# design.net
KiCad netlist of a schematic drawn in Altium Designer
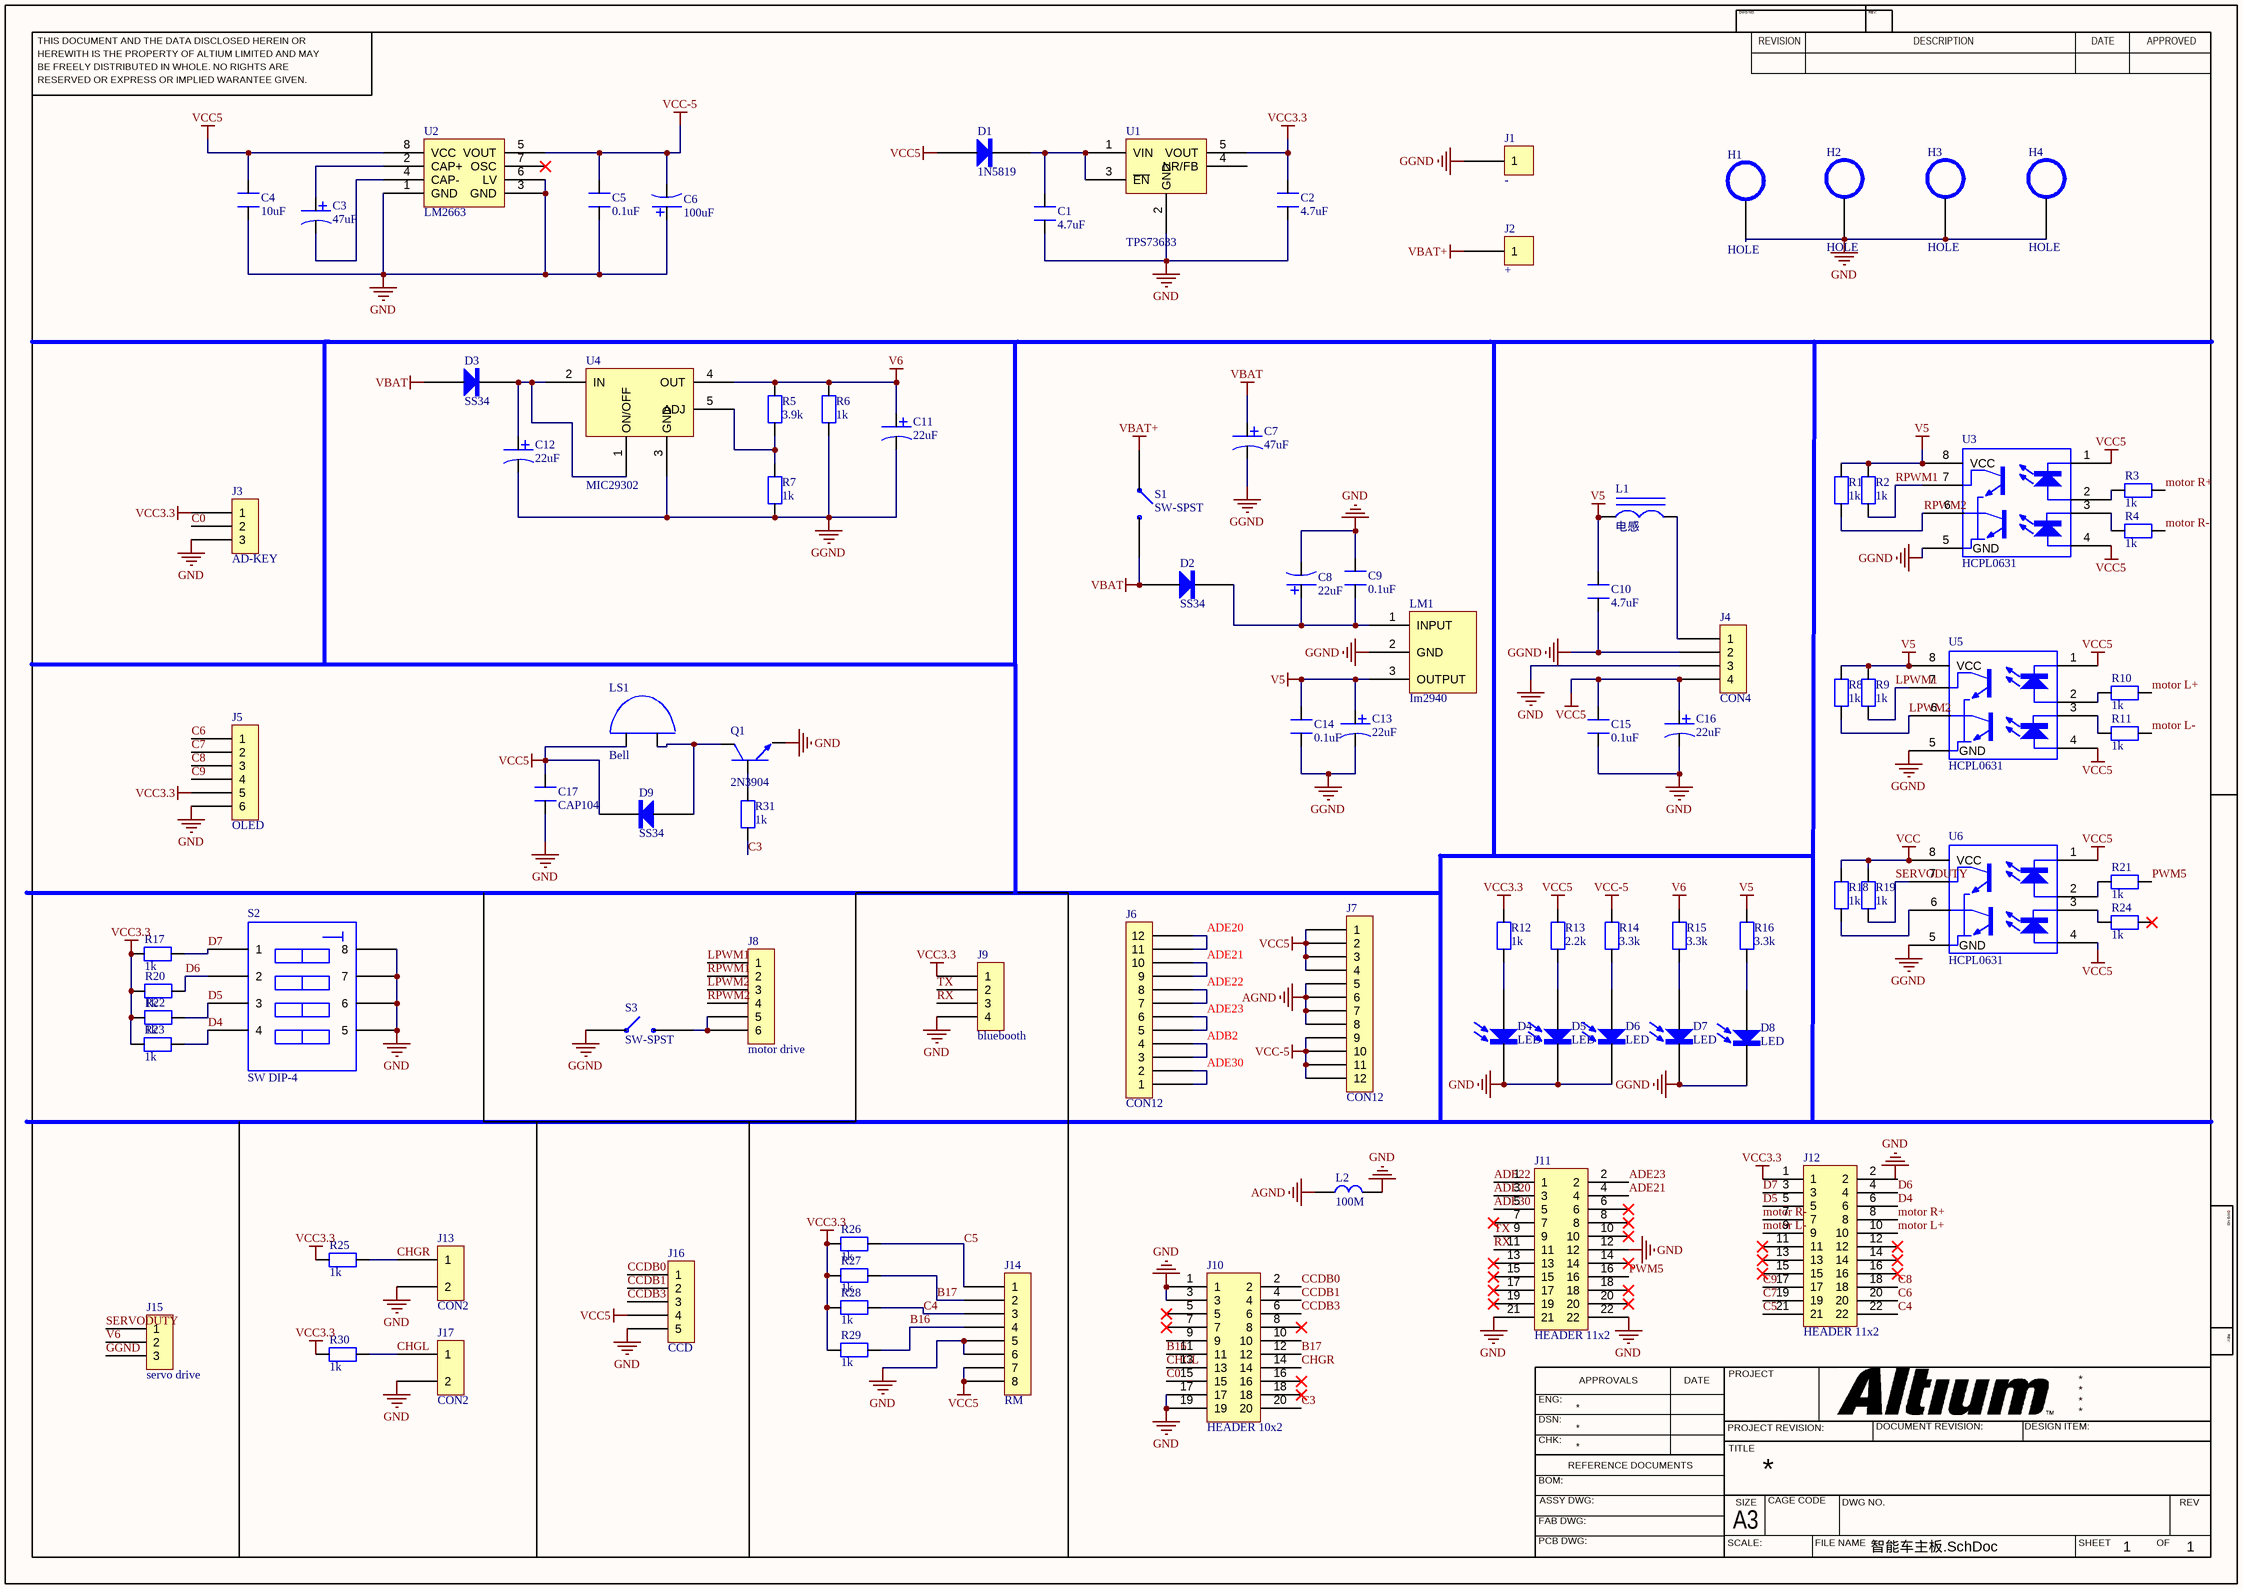
[diagram p0: 智能车主板.SchDoc]

(export (version "E")
  (design (tool "Eeschema 10.0.6"))
  (components
    (comp (ref "C1")
      (value "4.7uF")
      (footprint "0805C")
      (description "电容")
      (libsource (lib "智能车主板") (part "CAP"))
    )
    (comp (ref "C2")
      (value "4.7uF")
      (footprint "0805C")
      (description "电容")
      (libsource (lib "智能车主板") (part "CAP"))
    )
    (comp (ref "C3") (value "47uF") (footprint "B型钽电容_3528_21") (libsource (lib "智能车主板") (part "极性电容")))
    (comp (ref "C4")
      (value "10uF")
      (footprint "0805C")
      (description "电容")
      (libsource (lib "智能车主板") (part "CAP"))
    )
    (comp (ref "C5")
      (value "0.1uF")
      (footprint "0805C")
      (description "电容")
      (libsource (lib "智能车主板") (part "CAP"))
    )
    (comp (ref "C6") (value "100uF") (footprint "B型钽电容_3528_21") (libsource (lib "智能车主板") (part "极性电容")))
    (comp (ref "C7") (value "47uF") (footprint "B型钽电容_3528_21") (libsource (lib "智能车主板") (part "极性电容")))
    (comp (ref "C8") (value "22uF") (footprint "B型钽电容_3528_21") (libsource (lib "智能车主板") (part "极性电容")))
    (comp (ref "C9")
      (value "0.1uF")
      (footprint "0805C")
      (description "电容")
      (libsource (lib "智能车主板") (part "CAP"))
    )
    (comp (ref "C10")
      (value "4.7uF")
      (footprint "0805C")
      (description "电容")
      (libsource (lib "智能车主板") (part "CAP"))
    )
    (comp (ref "C11") (value "22uF") (footprint "B型钽电容_3528_21") (libsource (lib "智能车主板") (part "极性电容")))
    (comp (ref "C12") (value "22uF") (footprint "B型钽电容_3528_21") (libsource (lib "智能车主板") (part "极性电容")))
    (comp (ref "C13") (value "22uF") (footprint "B型钽电容_3528_21") (libsource (lib "智能车主板") (part "极性电容")))
    (comp (ref "C14")
      (value "0.1uF")
      (footprint "0805C")
      (description "电容")
      (libsource (lib "智能车主板") (part "CAP"))
    )
    (comp (ref "C15")
      (value "0.1uF")
      (footprint "0805C")
      (description "电容")
      (libsource (lib "智能车主板") (part "CAP"))
    )
    (comp (ref "C16") (value "22uF") (footprint "B型钽电容_3528_21") (libsource (lib "智能车主板") (part "极性电容")))
    (comp (ref "C17")
      (value "CAP104")
      (footprint "0805C")
      (description "电容")
      (libsource (lib "智能车主板") (part "CAP"))
    )
    (comp (ref "D1")
      (value "1N5819")
      (footprint "SOD-123")
      (description "二极管")
      (libsource (lib "智能车主板") (part "SS34"))
    )
    (comp (ref "D2")
      (value "SS34")
      (footprint "SOD-123")
      (description "二极管")
      (libsource (lib "智能车主板") (part "SS34"))
    )
    (comp (ref "D3")
      (value "SS34")
      (footprint "SOD-123")
      (description "二极管")
      (libsource (lib "智能车主板") (part "SS34"))
    )
    (comp (ref "D4") (value "LED") (footprint "0805D") (libsource (lib "智能车主板") (part "LED")))
    (comp (ref "D5") (value "LED") (footprint "0805D") (libsource (lib "智能车主板") (part "LED")))
    (comp (ref "D6") (value "LED") (footprint "0805D") (libsource (lib "智能车主板") (part "LED")))
    (comp (ref "D7") (value "LED") (footprint "0805D") (libsource (lib "智能车主板") (part "LED")))
    (comp (ref "D8") (value "LED") (footprint "0805D") (libsource (lib "智能车主板") (part "LED")))
    (comp (ref "D9")
      (value "SS34")
      (footprint "SOD-123")
      (description "二极管")
      (libsource (lib "智能车主板") (part "SS34"))
    )
    (comp (ref "H1") (value "HOLE") (footprint "铜柱孔3") (libsource (lib "智能车主板") (part "固定孔")))
    (comp (ref "H2") (value "HOLE") (footprint "铜柱孔3") (libsource (lib "智能车主板") (part "固定孔")))
    (comp (ref "H3") (value "HOLE") (footprint "铜柱孔3") (libsource (lib "智能车主板") (part "固定孔")))
    (comp (ref "H4") (value "HOLE") (footprint "铜柱孔3") (libsource (lib "智能车主板") (part "固定孔")))
    (comp (ref "J1") (value "-") (footprint "单面焊盘2*3MM_1PIN") (libsource (lib "智能车主板") (part "CON1")))
    (comp (ref "J2") (value "+") (footprint "单面焊盘2*3MM_1PIN") (libsource (lib "智能车主板") (part "CON1")))
    (comp (ref "J3") (value "AD-KEY") (footprint "HDR1X3") (libsource (lib "智能车主板") (part "CON3")))
    (comp (ref "J4") (value "CON4") (footprint "HDR1X4") (libsource (lib "智能车主板") (part "CON4")))
    (comp (ref "J5") (value "OLED") (footprint "HDR2X3") (libsource (lib "智能车主板") (part "CON6")))
    (comp (ref "J6") (value "CON12") (footprint "HDR2X6") (libsource (lib "") (part "CON12_1")))
    (comp (ref "J7") (value "CON12") (footprint "HDR2X6") (libsource (lib "智能车主板") (part "CON12")))
    (comp (ref "J8") (value "motor drive") (footprint "HDR2X3") (libsource (lib "智能车主板") (part "CON6")))
    (comp (ref "J9") (value "bluebooth") (footprint "HDR1X4") (libsource (lib "智能车主板") (part "CON4")))
    (comp (ref "J10")
      (value "HEADER 10x2")
      (footprint "HDR2X10")
      (description "排针")
      (libsource (lib "智能车主板") (part "HEADER 10x2"))
    )
    (comp (ref "J11")
      (value "HEADER 11x2")
      (footprint "HDR2X11")
      (description "排针")
      (libsource (lib "智能车主板") (part "HEADER 11x2"))
    )
    (comp (ref "J12")
      (value "HEADER 11x2")
      (footprint "HDR2X11")
      (description "排针")
      (libsource (lib "智能车主板") (part "HEADER 11x2"))
    )
    (comp (ref "J13") (value "CON2") (footprint "2PIN杜邦插座_1.27mm") (libsource (lib "智能车主板") (part "CON2")))
    (comp (ref "J14") (value "RM") (footprint "HDR2X4") (libsource (lib "智能车主板") (part "CON8")))
    (comp (ref "J15") (value "servo drive") (footprint "HDR1X3") (libsource (lib "智能车主板") (part "CON3")))
    (comp (ref "J16") (value "CCD") (footprint "HDR1X5") (libsource (lib "智能车主板") (part "CON5")))
    (comp (ref "J17") (value "CON2") (footprint "2PIN杜邦插座_1.27mm") (libsource (lib "智能车主板") (part "CON2")))
    (comp (ref "L1") (value "电感") (footprint "CDRH3D16_4.2*1.8") (libsource (lib "智能车主板") (part "INDUCTOR")))
    (comp (ref "L2") (value "100M") (footprint "0603L") (libsource (lib "智能车主板") (part "INDUCTOR_2")))
    (comp (ref "LM1")
      (value "Im2940")
      (footprint "SOT-223")
      (description "IC")
      (libsource (lib "智能车主板") (part "Im2940"))
    )
    (comp (ref "LS1") (value "Bell") (footprint "蜂鸣器侧装") (libsource (lib "智能车主板") (part "Bell")))
    (comp (ref "Q1")
      (value "2N3904")
      (footprint "TO-92A")
      (description "NPN General Purpose Amplifier")
      (libsource (lib "智能车主板") (part "2N3904"))
    )
    (comp (ref "R1")
      (value "1k")
      (footprint "0805_Res")
      (description "电阻")
      (libsource (lib "") (part "RES_1"))
    )
    (comp (ref "R2")
      (value "1k")
      (footprint "0805_Res")
      (description "电阻")
      (libsource (lib "") (part "RES_1"))
    )
    (comp (ref "R3")
      (value "1k")
      (footprint "0805_Res")
      (description "电阻")
      (libsource (lib "智能车主板") (part "RES"))
    )
    (comp (ref "R4")
      (value "1k")
      (footprint "0805_Res")
      (description "电阻")
      (libsource (lib "智能车主板") (part "RES"))
    )
    (comp (ref "R5")
      (value "3.9k")
      (footprint "0805_Res")
      (description "电阻")
      (libsource (lib "") (part "RES_1"))
    )
    (comp (ref "R6")
      (value "1k")
      (footprint "0805_Res")
      (description "电阻")
      (libsource (lib "") (part "RES_1"))
    )
    (comp (ref "R7")
      (value "1k")
      (footprint "0805_Res")
      (description "电阻")
      (libsource (lib "") (part "RES_1"))
    )
    (comp (ref "R8")
      (value "1k")
      (footprint "0805_Res")
      (description "电阻")
      (libsource (lib "") (part "RES_1"))
    )
    (comp (ref "R9")
      (value "1k")
      (footprint "0805_Res")
      (description "电阻")
      (libsource (lib "") (part "RES_1"))
    )
    (comp (ref "R10")
      (value "1k")
      (footprint "0805_Res")
      (description "电阻")
      (libsource (lib "智能车主板") (part "RES"))
    )
    (comp (ref "R11")
      (value "1k")
      (footprint "0805_Res")
      (description "电阻")
      (libsource (lib "智能车主板") (part "RES"))
    )
    (comp (ref "R12")
      (value "1k")
      (footprint "0805_Res")
      (description "电阻")
      (libsource (lib "") (part "RES_1"))
    )
    (comp (ref "R13")
      (value "2.2k")
      (footprint "0805_Res")
      (description "电阻")
      (libsource (lib "") (part "RES_1"))
    )
    (comp (ref "R14")
      (value "3.3k")
      (footprint "0805_Res")
      (description "电阻")
      (libsource (lib "") (part "RES_1"))
    )
    (comp (ref "R15")
      (value "3.3k")
      (footprint "0805_Res")
      (description "电阻")
      (libsource (lib "") (part "RES_1"))
    )
    (comp (ref "R16")
      (value "3.3k")
      (footprint "0805_Res")
      (description "电阻")
      (libsource (lib "") (part "RES_1"))
    )
    (comp (ref "R17")
      (value "1k")
      (footprint "0805_Res")
      (description "电阻")
      (libsource (lib "智能车主板") (part "RES"))
    )
    (comp (ref "R18")
      (value "1k")
      (footprint "0805_Res")
      (description "电阻")
      (libsource (lib "") (part "RES_1"))
    )
    (comp (ref "R19")
      (value "1k")
      (footprint "0805_Res")
      (description "电阻")
      (libsource (lib "") (part "RES_1"))
    )
    (comp (ref "R20")
      (value "1k")
      (footprint "0805_Res")
      (description "电阻")
      (libsource (lib "智能车主板") (part "RES"))
    )
    (comp (ref "R21")
      (value "1k")
      (footprint "0805_Res")
      (description "电阻")
      (libsource (lib "智能车主板") (part "RES"))
    )
    (comp (ref "R22")
      (value "1k")
      (footprint "0805_Res")
      (description "电阻")
      (libsource (lib "智能车主板") (part "RES"))
    )
    (comp (ref "R23")
      (value "1k")
      (footprint "0805_Res")
      (description "电阻")
      (libsource (lib "智能车主板") (part "RES"))
    )
    (comp (ref "R24")
      (value "1k")
      (footprint "0805_Res")
      (description "电阻")
      (libsource (lib "智能车主板") (part "RES"))
    )
    (comp (ref "R25")
      (value "1k")
      (footprint "0805_Res")
      (description "电阻")
      (libsource (lib "智能车主板") (part "RES"))
    )
    (comp (ref "R26")
      (value "1k")
      (footprint "0805_Res")
      (description "电阻")
      (libsource (lib "智能车主板") (part "RES"))
    )
    (comp (ref "R27")
      (value "1k")
      (footprint "0805_Res")
      (description "电阻")
      (libsource (lib "智能车主板") (part "RES"))
    )
    (comp (ref "R28")
      (value "1k")
      (footprint "0805_Res")
      (description "电阻")
      (libsource (lib "智能车主板") (part "RES"))
    )
    (comp (ref "R29")
      (value "1k")
      (footprint "0805_Res")
      (description "电阻")
      (libsource (lib "智能车主板") (part "RES"))
    )
    (comp (ref "R30")
      (value "1k")
      (footprint "0805_Res")
      (description "电阻")
      (libsource (lib "智能车主板") (part "RES"))
    )
    (comp (ref "R31")
      (value "1k")
      (footprint "0805_Res")
      (description "电阻")
      (libsource (lib "") (part "RES_1"))
    )
    (comp (ref "S1") (value "SW-SPST") (footprint "开关") (libsource (lib "智能车主板") (part "SW-SPST")))
    (comp (ref "S2") (value "SW DIP-4") (footprint "4路拨码开关") (libsource (lib "智能车主板") (part "SW DIP-4")))
    (comp (ref "S3") (value "SW-SPST") (footprint "开关") (libsource (lib "智能车主板") (part "SW-SPST")))
    (comp (ref "U1")
      (value "TPS73633")
      (footprint "SOT23_5-LEADS")
      (description "IC")
      (libsource (lib "智能车主板") (part "TPS73633"))
    )
    (comp (ref "U2")
      (value "LM2663")
      (footprint "SOP-8")
      (description "IC")
      (libsource (lib "智能车主板") (part "LM2663"))
    )
    (comp (ref "U3")
      (value "HCPL0631")
      (footprint "SOP-8")
      (description "光耦")
      (libsource (lib "智能车主板") (part "HCPL0631"))
    )
    (comp (ref "U4")
      (value "MIC29302")
      (footprint "TO_263_5(10.5*8.4mm)")
      (description "IC")
      (libsource (lib "智能车主板") (part "MIC29302"))
    )
    (comp (ref "U5")
      (value "HCPL0631")
      (footprint "SOP-8")
      (description "光耦")
      (libsource (lib "智能车主板") (part "HCPL0631"))
    )
    (comp (ref "U6")
      (value "HCPL0631")
      (footprint "SOP-8")
      (description "光耦")
      (libsource (lib "智能车主板") (part "HCPL0631"))
    )
  )
  (nets
    (net (code "1") (name "/ADB2") (class "Default")
      (node (ref "J6") (pin "3") (pinfunction "3_3") (pintype "passive"))
      (node (ref "J6") (pin "4") (pinfunction "4_4") (pintype "passive"))
    )
    (net (code "2") (name "/ADE20") (class "Default")
      (node (ref "J11") (pin "3") (pinfunction "3_3") (pintype "passive"))
      (node (ref "J6") (pin "11") (pinfunction "11_11") (pintype "passive"))
      (node (ref "J6") (pin "12") (pinfunction "12_12") (pintype "passive"))
    )
    (net (code "3") (name "/ADE21") (class "Default")
      (node (ref "J11") (pin "4") (pinfunction "4_4") (pintype "passive"))
      (node (ref "J6") (pin "10") (pinfunction "10_10") (pintype "passive"))
      (node (ref "J6") (pin "9") (pinfunction "9_9") (pintype "passive"))
    )
    (net (code "4") (name "/ADE22") (class "Default")
      (node (ref "J11") (pin "1") (pinfunction "1_1") (pintype "passive"))
      (node (ref "J6") (pin "7") (pinfunction "7_7") (pintype "passive"))
      (node (ref "J6") (pin "8") (pinfunction "8_8") (pintype "passive"))
    )
    (net (code "5") (name "/ADE23") (class "Default")
      (node (ref "J11") (pin "2") (pinfunction "2_2") (pintype "passive"))
      (node (ref "J6") (pin "5") (pinfunction "5_5") (pintype "passive"))
      (node (ref "J6") (pin "6") (pinfunction "6_6") (pintype "passive"))
    )
    (net (code "6") (name "/ADE30") (class "Default")
      (node (ref "J11") (pin "5") (pinfunction "5_5") (pintype "passive"))
      (node (ref "J6") (pin "1") (pinfunction "1_1") (pintype "passive"))
      (node (ref "J6") (pin "2") (pinfunction "2_2") (pintype "passive"))
    )
    (net (code "7") (name "/B16") (class "Default")
      (node (ref "J10") (pin "11") (pinfunction "11_11") (pintype "passive"))
      (node (ref "J14") (pin "4") (pinfunction "4_4") (pintype "passive"))
      (node (ref "R29") (pin "1") (pinfunction "1_1") (pintype "passive"))
    )
    (net (code "8") (name "/B17") (class "Default")
      (node (ref "J10") (pin "12") (pinfunction "12_12") (pintype "passive"))
      (node (ref "J14") (pin "2") (pinfunction "2_2") (pintype "passive"))
      (node (ref "R27") (pin "1") (pinfunction "1_1") (pintype "passive"))
    )
    (net (code "9") (name "/C0") (class "Default")
      (node (ref "J10") (pin "15") (pinfunction "15_15") (pintype "passive"))
      (node (ref "J3") (pin "2") (pinfunction "2_2") (pintype "passive"))
    )
    (net (code "10") (name "/C3") (class "Default")
      (node (ref "J10") (pin "20") (pinfunction "20_20") (pintype "passive"))
      (node (ref "R31") (pin "1") (pinfunction "1_1") (pintype "passive"))
    )
    (net (code "11") (name "/C4") (class "Default")
      (node (ref "J12") (pin "22") (pinfunction "22_22") (pintype "passive"))
      (node (ref "J14") (pin "3") (pinfunction "3_3") (pintype "passive"))
      (node (ref "R28") (pin "1") (pinfunction "1_1") (pintype "passive"))
    )
    (net (code "12") (name "/C5") (class "Default")
      (node (ref "J12") (pin "21") (pinfunction "21_21") (pintype "passive"))
      (node (ref "J14") (pin "1") (pinfunction "1_1") (pintype "passive"))
      (node (ref "R26") (pin "1") (pinfunction "1_1") (pintype "passive"))
    )
    (net (code "13") (name "/C6") (class "Default")
      (node (ref "J12") (pin "20") (pinfunction "20_20") (pintype "passive"))
      (node (ref "J5") (pin "1") (pinfunction "1_1") (pintype "passive"))
    )
    (net (code "14") (name "/C7") (class "Default")
      (node (ref "J12") (pin "19") (pinfunction "19_19") (pintype "passive"))
      (node (ref "J5") (pin "2") (pinfunction "2_2") (pintype "passive"))
    )
    (net (code "15") (name "/C8") (class "Default")
      (node (ref "J12") (pin "18") (pinfunction "18_18") (pintype "passive"))
      (node (ref "J5") (pin "3") (pinfunction "3_3") (pintype "passive"))
    )
    (net (code "16") (name "/C9") (class "Default")
      (node (ref "J12") (pin "17") (pinfunction "17_17") (pintype "passive"))
      (node (ref "J5") (pin "4") (pinfunction "4_4") (pintype "passive"))
    )
    (net (code "17") (name "/CCDB0") (class "Default")
      (node (ref "J10") (pin "2") (pinfunction "2_2") (pintype "passive"))
      (node (ref "J16") (pin "1") (pinfunction "1_1") (pintype "passive"))
    )
    (net (code "18") (name "/CCDB1") (class "Default")
      (node (ref "J10") (pin "4") (pinfunction "4_4") (pintype "passive"))
      (node (ref "J16") (pin "2") (pinfunction "2_2") (pintype "passive"))
    )
    (net (code "19") (name "/CCDB3") (class "Default")
      (node (ref "J10") (pin "6") (pinfunction "6_6") (pintype "passive"))
      (node (ref "J16") (pin "3") (pinfunction "3_3") (pintype "passive"))
    )
    (net (code "20") (name "/CHGL") (class "Default")
      (node (ref "J10") (pin "13") (pinfunction "13_13") (pintype "passive"))
      (node (ref "J17") (pin "1") (pinfunction "1_1") (pintype "passive"))
      (node (ref "R30") (pin "1") (pinfunction "1_1") (pintype "passive"))
    )
    (net (code "21") (name "/CHGR") (class "Default")
      (node (ref "J10") (pin "14") (pinfunction "14_14") (pintype "passive"))
      (node (ref "J13") (pin "1") (pinfunction "1_1") (pintype "passive"))
      (node (ref "R25") (pin "1") (pinfunction "1_1") (pintype "passive"))
    )
    (net (code "22") (name "/D4") (class "Default")
      (node (ref "J12") (pin "6") (pinfunction "6_6") (pintype "passive"))
      (node (ref "R23") (pin "1") (pinfunction "1_1") (pintype "passive"))
      (node (ref "S2") (pin "4") (pinfunction "4_4") (pintype "passive"))
    )
    (net (code "23") (name "/D5") (class "Default")
      (node (ref "J12") (pin "5") (pinfunction "5_5") (pintype "passive"))
      (node (ref "R22") (pin "1") (pinfunction "1_1") (pintype "passive"))
      (node (ref "S2") (pin "3") (pinfunction "3_3") (pintype "passive"))
    )
    (net (code "24") (name "/D6") (class "Default")
      (node (ref "J12") (pin "4") (pinfunction "4_4") (pintype "passive"))
      (node (ref "R20") (pin "1") (pinfunction "1_1") (pintype "passive"))
      (node (ref "S2") (pin "2") (pinfunction "2_2") (pintype "passive"))
    )
    (net (code "25") (name "/D7") (class "Default")
      (node (ref "J12") (pin "3") (pinfunction "3_3") (pintype "passive"))
      (node (ref "R17") (pin "1") (pinfunction "1_1") (pintype "passive"))
      (node (ref "S2") (pin "1") (pinfunction "1_1") (pintype "passive"))
    )
    (net (code "26") (name "/LPWM1") (class "Default")
      (node (ref "J8") (pin "1") (pinfunction "1_1") (pintype "passive"))
      (node (ref "R9") (pin "1") (pinfunction "1_1") (pintype "passive"))
      (node (ref "U5") (pin "7") (pinfunction "7_7") (pintype "passive"))
    )
    (net (code "27") (name "/LPWM2") (class "Default")
      (node (ref "J8") (pin "3") (pinfunction "3_3") (pintype "passive"))
      (node (ref "R8") (pin "1") (pinfunction "1_1") (pintype "passive"))
      (node (ref "U5") (pin "6") (pinfunction "6_6") (pintype "passive"))
    )
    (net (code "28") (name "/PWM5") (class "Default")
      (node (ref "J11") (pin "16") (pinfunction "16_16") (pintype "passive"))
      (node (ref "R21") (pin "1") (pinfunction "1_1") (pintype "passive"))
    )
    (net (code "29") (name "/RPWM1") (class "Default")
      (node (ref "J8") (pin "2") (pinfunction "2_2") (pintype "passive"))
      (node (ref "R2") (pin "1") (pinfunction "1_1") (pintype "passive"))
      (node (ref "U3") (pin "7") (pinfunction "7_7") (pintype "passive"))
    )
    (net (code "30") (name "/RPWM2") (class "Default")
      (node (ref "J8") (pin "4") (pinfunction "4_4") (pintype "passive"))
      (node (ref "R1") (pin "1") (pinfunction "1_1") (pintype "passive"))
      (node (ref "U3") (pin "6") (pinfunction "6_6") (pintype "passive"))
    )
    (net (code "31") (name "/RX") (class "Default")
      (node (ref "J11") (pin "11") (pinfunction "11_11") (pintype "passive"))
      (node (ref "J9") (pin "3") (pinfunction "3_3") (pintype "passive"))
    )
    (net (code "32") (name "/SERVODUTY") (class "Default")
      (node (ref "J15") (pin "1") (pinfunction "1_1") (pintype "passive"))
      (node (ref "R19") (pin "1") (pinfunction "1_1") (pintype "passive"))
      (node (ref "U6") (pin "7") (pinfunction "7_7") (pintype "passive"))
    )
    (net (code "33") (name "/TX") (class "Default")
      (node (ref "J11") (pin "9") (pinfunction "9_9") (pintype "passive"))
      (node (ref "J9") (pin "2") (pinfunction "2_2") (pintype "passive"))
    )
    (net (code "34") (name "/motor L+") (class "Default")
      (node (ref "J12") (pin "10") (pinfunction "10_10") (pintype "passive"))
      (node (ref "R10") (pin "1") (pinfunction "1_1") (pintype "passive"))
    )
    (net (code "35") (name "/motor L-") (class "Default")
      (node (ref "J12") (pin "9") (pinfunction "9_9") (pintype "passive"))
      (node (ref "R11") (pin "1") (pinfunction "1_1") (pintype "passive"))
    )
    (net (code "36") (name "/motor R+") (class "Default")
      (node (ref "J12") (pin "8") (pinfunction "8_8") (pintype "passive"))
      (node (ref "R3") (pin "1") (pinfunction "1_1") (pintype "passive"))
    )
    (net (code "37") (name "/motor R-") (class "Default")
      (node (ref "J12") (pin "7") (pinfunction "7_7") (pintype "passive"))
      (node (ref "R4") (pin "1") (pinfunction "1_1") (pintype "passive"))
    )
    (net (code "38") (name "AGND") (class "Default")
      (node (ref "J7") (pin "5") (pinfunction "5_5") (pintype "passive"))
      (node (ref "J7") (pin "6") (pinfunction "6_6") (pintype "passive"))
      (node (ref "J7") (pin "7") (pinfunction "7_7") (pintype "passive"))
      (node (ref "J7") (pin "8") (pinfunction "8_8") (pintype "passive"))
      (node (ref "L2") (pin "1") (pinfunction "1_1") (pintype "passive"))
    )
    (net (code "39") (name "GGND") (class "Default")
      (node (ref "C10") (pin "1") (pinfunction "1_1") (pintype "passive"))
      (node (ref "C11") (pin "2") (pinfunction "2_2") (pintype "passive"))
      (node (ref "C12") (pin "2") (pinfunction "2_2") (pintype "passive"))
      (node (ref "C13") (pin "2") (pinfunction "2_2") (pintype "passive"))
      (node (ref "C14") (pin "1") (pinfunction "1_1") (pintype "passive"))
      (node (ref "C7") (pin "2") (pinfunction "2_2") (pintype "passive"))
      (node (ref "D7") (pin "2") (pinfunction "2_2") (pintype "passive"))
      (node (ref "D8") (pin "2") (pinfunction "2_2") (pintype "passive"))
      (node (ref "J1") (pin "1") (pinfunction "1_1") (pintype "passive"))
      (node (ref "J15") (pin "3") (pinfunction "3_3") (pintype "passive"))
      (node (ref "J4") (pin "2") (pinfunction "2_2") (pintype "passive"))
      (node (ref "LM1") (pin "2") (pinfunction "GND_2") (pintype "passive"))
      (node (ref "R6") (pin "1") (pinfunction "1_1") (pintype "passive"))
      (node (ref "R7") (pin "1") (pinfunction "1_1") (pintype "passive"))
      (node (ref "S3") (pin "2") (pinfunction "2_2") (pintype "passive"))
      (node (ref "U3") (pin "5") (pinfunction "GND_5") (pintype "passive"))
      (node (ref "U4") (pin "3") (pinfunction "GND_3") (pintype "passive"))
      (node (ref "U5") (pin "5") (pinfunction "GND_5") (pintype "passive"))
      (node (ref "U6") (pin "5") (pinfunction "GND_5") (pintype "passive"))
    )
    (net (code "40") (name "GND") (class "Default")
      (node (ref "C1") (pin "1") (pinfunction "1_1") (pintype "passive"))
      (node (ref "C15") (pin "1") (pinfunction "1_1") (pintype "passive"))
      (node (ref "C16") (pin "2") (pinfunction "2_2") (pintype "passive"))
      (node (ref "C17") (pin "1") (pinfunction "1_1") (pintype "passive"))
      (node (ref "C2") (pin "1") (pinfunction "1_1") (pintype "passive"))
      (node (ref "C4") (pin "1") (pinfunction "1_1") (pintype "passive"))
      (node (ref "C5") (pin "1") (pinfunction "1_1") (pintype "passive"))
      (node (ref "C6") (pin "1") (pinfunction "1_1") (pintype "passive"))
      (node (ref "C8") (pin "2") (pinfunction "2_2") (pintype "passive"))
      (node (ref "C9") (pin "2") (pinfunction "2_2") (pintype "passive"))
      (node (ref "D4") (pin "2") (pinfunction "2_2") (pintype "passive"))
      (node (ref "D5") (pin "2") (pinfunction "2_2") (pintype "passive"))
      (node (ref "D6") (pin "2") (pinfunction "2_2") (pintype "passive"))
      (node (ref "H1") (pin "11") (pinfunction "11_11") (pintype "passive"))
      (node (ref "H2") (pin "11") (pinfunction "11_11") (pintype "passive"))
      (node (ref "H3") (pin "11") (pinfunction "11_11") (pintype "passive"))
      (node (ref "H4") (pin "11") (pinfunction "11_11") (pintype "passive"))
      (node (ref "J10") (pin "1") (pinfunction "1_1") (pintype "passive"))
      (node (ref "J10") (pin "17") (pinfunction "17_17") (pintype "passive"))
      (node (ref "J10") (pin "19") (pinfunction "19_19") (pintype "passive"))
      (node (ref "J10") (pin "3") (pinfunction "3_3") (pintype "passive"))
      (node (ref "J11") (pin "12") (pinfunction "12_12") (pintype "passive"))
      (node (ref "J11") (pin "21") (pinfunction "21_21") (pintype "passive"))
      (node (ref "J11") (pin "22") (pinfunction "22_22") (pintype "passive"))
      (node (ref "J13") (pin "2") (pinfunction "2_2") (pintype "passive"))
      (node (ref "J14") (pin "5") (pinfunction "5_5") (pintype "passive"))
      (node (ref "J14") (pin "6") (pinfunction "6_6") (pintype "passive"))
      (node (ref "J16") (pin "5") (pinfunction "5_5") (pintype "passive"))
      (node (ref "J17") (pin "2") (pinfunction "2_2") (pintype "passive"))
      (node (ref "J3") (pin "3") (pinfunction "3_3") (pintype "passive"))
      (node (ref "J4") (pin "3") (pinfunction "3_3") (pintype "passive"))
      (node (ref "J5") (pin "6") (pinfunction "6_6") (pintype "passive"))
      (node (ref "J9") (pin "4") (pinfunction "4_4") (pintype "passive"))
      (node (ref "L2") (pin "2") (pinfunction "2_2") (pintype "passive"))
      (node (ref "Q1") (pin "2") (pinfunction "2_2") (pintype "passive"))
      (node (ref "S2") (pin "5") (pinfunction "5_5") (pintype "passive"))
      (node (ref "S2") (pin "6") (pinfunction "6_6") (pintype "passive"))
      (node (ref "S2") (pin "7") (pinfunction "7_7") (pintype "passive"))
      (node (ref "S2") (pin "8") (pinfunction "8_8") (pintype "passive"))
      (node (ref "U1") (pin "2") (pinfunction "GND_2") (pintype "passive"))
      (node (ref "U2") (pin "1") (pinfunction "GND_1") (pintype "passive"))
      (node (ref "U2") (pin "3") (pinfunction "GND_3") (pintype "passive"))
      (node (ref "U2") (pin "6") (pinfunction "LV_6") (pintype "passive"))
    )
    (net (code "41") (name "Net-(D4-Pad1)") (class "Default")
      (node (ref "D4") (pin "1") (pinfunction "1_1") (pintype "passive"))
      (node (ref "R12") (pin "1") (pinfunction "1_1") (pintype "passive"))
    )
    (net (code "42") (name "Net-(D5-Pad1)") (class "Default")
      (node (ref "D5") (pin "1") (pinfunction "1_1") (pintype "passive"))
      (node (ref "R13") (pin "1") (pinfunction "1_1") (pintype "passive"))
    )
    (net (code "43") (name "Net-(D6-Pad1)") (class "Default")
      (node (ref "D6") (pin "1") (pinfunction "1_1") (pintype "passive"))
      (node (ref "R14") (pin "1") (pinfunction "1_1") (pintype "passive"))
    )
    (net (code "44") (name "Net-(D7-Pad1)") (class "Default")
      (node (ref "D7") (pin "1") (pinfunction "1_1") (pintype "passive"))
      (node (ref "R15") (pin "1") (pinfunction "1_1") (pintype "passive"))
    )
    (net (code "45") (name "Net-(D8-Pad1)") (class "Default")
      (node (ref "D8") (pin "1") (pinfunction "1_1") (pintype "passive"))
      (node (ref "R16") (pin "1") (pinfunction "1_1") (pintype "passive"))
    )
    (net (code "46") (name "Net-(D9-Pad1)") (class "Default")
      (node (ref "D9") (pin "1") (pinfunction "1_1") (pintype "passive"))
      (node (ref "LS1") (pin "2") (pinfunction "2_2") (pintype "passive"))
      (node (ref "Q1") (pin "1") (pinfunction "1_1") (pintype "passive"))
    )
    (net (code "47") (name "Net-(J4-Pad1)") (class "Default")
      (node (ref "J4") (pin "1") (pinfunction "1_1") (pintype "passive"))
      (node (ref "L1") (pin "2") (pinfunction "2_2") (pintype "passive"))
    )
    (net (code "48") (name "Net-(J8-Pad5)") (class "Default")
      (node (ref "J8") (pin "5") (pinfunction "5_5") (pintype "passive"))
      (node (ref "J8") (pin "6") (pinfunction "6_6") (pintype "passive"))
      (node (ref "S3") (pin "1") (pinfunction "1_1") (pintype "passive"))
    )
    (net (code "49") (name "Net-(LM1-INPUT)") (class "Default")
      (node (ref "C8") (pin "1") (pinfunction "1_1") (pintype "passive"))
      (node (ref "C9") (pin "1") (pinfunction "1_1") (pintype "passive"))
      (node (ref "D2") (pin "2") (pinfunction "2_2") (pintype "passive"))
      (node (ref "LM1") (pin "1") (pinfunction "INPUT_1") (pintype "passive"))
    )
    (net (code "50") (name "Net-(Q1-Pad3)") (class "Default")
      (node (ref "Q1") (pin "3") (pinfunction "3_3") (pintype "passive"))
      (node (ref "R31") (pin "2") (pinfunction "2_2") (pintype "passive"))
    )
    (net (code "51") (name "Net-(R3-Pad2)") (class "Default")
      (node (ref "R3") (pin "2") (pinfunction "2_2") (pintype "passive"))
      (node (ref "U3") (pin "2") (pinfunction "2_2") (pintype "passive"))
    )
    (net (code "52") (name "Net-(R4-Pad2)") (class "Default")
      (node (ref "R4") (pin "2") (pinfunction "2_2") (pintype "passive"))
      (node (ref "U3") (pin "3") (pinfunction "3_3") (pintype "passive"))
    )
    (net (code "53") (name "Net-(R10-Pad2)") (class "Default")
      (node (ref "R10") (pin "2") (pinfunction "2_2") (pintype "passive"))
      (node (ref "U5") (pin "2") (pinfunction "2_2") (pintype "passive"))
    )
    (net (code "54") (name "Net-(R11-Pad2)") (class "Default")
      (node (ref "R11") (pin "2") (pinfunction "2_2") (pintype "passive"))
      (node (ref "U5") (pin "3") (pinfunction "3_3") (pintype "passive"))
    )
    (net (code "55") (name "Net-(R18-Pad1)") (class "Default")
      (node (ref "R18") (pin "1") (pinfunction "1_1") (pintype "passive"))
      (node (ref "U6") (pin "6") (pinfunction "6_6") (pintype "passive"))
    )
    (net (code "56") (name "Net-(R21-Pad2)") (class "Default")
      (node (ref "R21") (pin "2") (pinfunction "2_2") (pintype "passive"))
      (node (ref "U6") (pin "2") (pinfunction "2_2") (pintype "passive"))
    )
    (net (code "57") (name "Net-(R24-Pad2)") (class "Default")
      (node (ref "R24") (pin "2") (pinfunction "2_2") (pintype "passive"))
      (node (ref "U6") (pin "3") (pinfunction "3_3") (pintype "passive"))
    )
    (net (code "58") (name "Net-(U1-VIN)") (class "Default")
      (node (ref "C1") (pin "2") (pinfunction "2_2") (pintype "passive"))
      (node (ref "D1") (pin "2") (pinfunction "2_2") (pintype "passive"))
      (node (ref "U1") (pin "1") (pinfunction "VIN_1") (pintype "passive"))
      (node (ref "U1") (pin "3") (pinfunction "~{EN}_3") (pintype "passive"))
    )
    (net (code "59") (name "Net-(U2-CAP+)") (class "Default")
      (node (ref "C3") (pin "1") (pinfunction "1_1") (pintype "passive"))
      (node (ref "U2") (pin "2") (pinfunction "CAP+_2") (pintype "passive"))
    )
    (net (code "60") (name "Net-(U2-CAP-)") (class "Default")
      (node (ref "C3") (pin "2") (pinfunction "2_2") (pintype "passive"))
      (node (ref "U2") (pin "4") (pinfunction "CAP-_4") (pintype "passive"))
    )
    (net (code "61") (name "Net-(U4-ADJ)") (class "Default")
      (node (ref "R5") (pin "1") (pinfunction "1_1") (pintype "passive"))
      (node (ref "R7") (pin "2") (pinfunction "2_2") (pintype "passive"))
      (node (ref "U4") (pin "5") (pinfunction "ADJ_5") (pintype "passive"))
    )
    (net (code "62") (name "Net-(U4-IN)") (class "Default")
      (node (ref "C12") (pin "1") (pinfunction "1_1") (pintype "passive"))
      (node (ref "D3") (pin "2") (pinfunction "2_2") (pintype "passive"))
      (node (ref "U4") (pin "1") (pinfunction "ON/OFF_1") (pintype "passive"))
      (node (ref "U4") (pin "2") (pinfunction "IN_2") (pintype "passive"))
    )
    (net (code "63") (name "V5") (class "Default")
      (node (ref "C10") (pin "2") (pinfunction "2_2") (pintype "passive"))
      (node (ref "C13") (pin "1") (pinfunction "1_1") (pintype "passive"))
      (node (ref "C14") (pin "2") (pinfunction "2_2") (pintype "passive"))
      (node (ref "L1") (pin "1") (pinfunction "1_1") (pintype "passive"))
      (node (ref "LM1") (pin "3") (pinfunction "OUTPUT_3") (pintype "passive"))
      (node (ref "R1") (pin "2") (pinfunction "2_2") (pintype "passive"))
      (node (ref "R16") (pin "2") (pinfunction "2_2") (pintype "passive"))
      (node (ref "R2") (pin "2") (pinfunction "2_2") (pintype "passive"))
      (node (ref "R8") (pin "2") (pinfunction "2_2") (pintype "passive"))
      (node (ref "R9") (pin "2") (pinfunction "2_2") (pintype "passive"))
      (node (ref "U3") (pin "8") (pinfunction "VCC_8") (pintype "passive"))
      (node (ref "U5") (pin "8") (pinfunction "VCC_8") (pintype "passive"))
    )
    (net (code "64") (name "V6") (class "Default")
      (node (ref "C11") (pin "1") (pinfunction "1_1") (pintype "passive"))
      (node (ref "J15") (pin "2") (pinfunction "2_2") (pintype "passive"))
      (node (ref "R15") (pin "2") (pinfunction "2_2") (pintype "passive"))
      (node (ref "R5") (pin "2") (pinfunction "2_2") (pintype "passive"))
      (node (ref "R6") (pin "2") (pinfunction "2_2") (pintype "passive"))
      (node (ref "U4") (pin "4") (pinfunction "OUT_4") (pintype "passive"))
    )
    (net (code "65") (name "VBAT") (class "Default")
      (node (ref "C7") (pin "1") (pinfunction "1_1") (pintype "passive"))
      (node (ref "D2") (pin "1") (pinfunction "1_1") (pintype "passive"))
      (node (ref "D3") (pin "1") (pinfunction "1_1") (pintype "passive"))
      (node (ref "S1") (pin "1") (pinfunction "1_1") (pintype "passive"))
    )
    (net (code "66") (name "VBAT+") (class "Default")
      (node (ref "J2") (pin "1") (pinfunction "1_1") (pintype "passive"))
      (node (ref "S1") (pin "2") (pinfunction "2_2") (pintype "passive"))
    )
    (net (code "67") (name "VCC") (class "Default")
      (node (ref "R18") (pin "2") (pinfunction "2_2") (pintype "passive"))
      (node (ref "R19") (pin "2") (pinfunction "2_2") (pintype "passive"))
      (node (ref "U6") (pin "8") (pinfunction "VCC_8") (pintype "passive"))
    )
    (net (code "68") (name "VCC-5") (class "Default")
      (node (ref "C5") (pin "2") (pinfunction "2_2") (pintype "passive"))
      (node (ref "C6") (pin "2") (pinfunction "2_2") (pintype "passive"))
      (node (ref "J7") (pin "10") (pinfunction "10_10") (pintype "passive"))
      (node (ref "J7") (pin "11") (pinfunction "11_11") (pintype "passive"))
      (node (ref "J7") (pin "12") (pinfunction "12_12") (pintype "passive"))
      (node (ref "J7") (pin "9") (pinfunction "9_9") (pintype "passive"))
      (node (ref "R14") (pin "2") (pinfunction "2_2") (pintype "passive"))
      (node (ref "U2") (pin "5") (pinfunction "VOUT_5") (pintype "passive"))
    )
    (net (code "69") (name "VCC3.3") (class "Default")
      (node (ref "C2") (pin "2") (pinfunction "2_2") (pintype "passive"))
      (node (ref "J12") (pin "1") (pinfunction "1_1") (pintype "passive"))
      (node (ref "J3") (pin "1") (pinfunction "1_1") (pintype "passive"))
      (node (ref "J5") (pin "5") (pinfunction "5_5") (pintype "passive"))
      (node (ref "J9") (pin "1") (pinfunction "1_1") (pintype "passive"))
      (node (ref "R12") (pin "2") (pinfunction "2_2") (pintype "passive"))
      (node (ref "R17") (pin "2") (pinfunction "2_2") (pintype "passive"))
      (node (ref "R20") (pin "2") (pinfunction "2_2") (pintype "passive"))
      (node (ref "R22") (pin "2") (pinfunction "2_2") (pintype "passive"))
      (node (ref "R23") (pin "2") (pinfunction "2_2") (pintype "passive"))
      (node (ref "R25") (pin "2") (pinfunction "2_2") (pintype "passive"))
      (node (ref "R26") (pin "2") (pinfunction "2_2") (pintype "passive"))
      (node (ref "R27") (pin "2") (pinfunction "2_2") (pintype "passive"))
      (node (ref "R28") (pin "2") (pinfunction "2_2") (pintype "passive"))
      (node (ref "R29") (pin "2") (pinfunction "2_2") (pintype "passive"))
      (node (ref "R30") (pin "2") (pinfunction "2_2") (pintype "passive"))
      (node (ref "U1") (pin "5") (pinfunction "VOUT_5") (pintype "passive"))
    )
    (net (code "70") (name "VCC5") (class "Default")
      (node (ref "C15") (pin "2") (pinfunction "2_2") (pintype "passive"))
      (node (ref "C16") (pin "1") (pinfunction "1_1") (pintype "passive"))
      (node (ref "C17") (pin "2") (pinfunction "2_2") (pintype "passive"))
      (node (ref "C4") (pin "2") (pinfunction "2_2") (pintype "passive"))
      (node (ref "D1") (pin "1") (pinfunction "1_1") (pintype "passive"))
      (node (ref "D9") (pin "2") (pinfunction "2_2") (pintype "passive"))
      (node (ref "J14") (pin "7") (pinfunction "7_7") (pintype "passive"))
      (node (ref "J14") (pin "8") (pinfunction "8_8") (pintype "passive"))
      (node (ref "J16") (pin "4") (pinfunction "4_4") (pintype "passive"))
      (node (ref "J4") (pin "4") (pinfunction "4_4") (pintype "passive"))
      (node (ref "J7") (pin "1") (pinfunction "1_1") (pintype "passive"))
      (node (ref "J7") (pin "2") (pinfunction "2_2") (pintype "passive"))
      (node (ref "J7") (pin "3") (pinfunction "3_3") (pintype "passive"))
      (node (ref "J7") (pin "4") (pinfunction "4_4") (pintype "passive"))
      (node (ref "LS1") (pin "1") (pinfunction "1_1") (pintype "passive"))
      (node (ref "R13") (pin "2") (pinfunction "2_2") (pintype "passive"))
      (node (ref "U2") (pin "8") (pinfunction "VCC_8") (pintype "passive"))
      (node (ref "U3") (pin "1") (pinfunction "1_1") (pintype "passive"))
      (node (ref "U3") (pin "4") (pinfunction "4_4") (pintype "passive"))
      (node (ref "U5") (pin "1") (pinfunction "1_1") (pintype "passive"))
      (node (ref "U5") (pin "4") (pinfunction "4_4") (pintype "passive"))
      (node (ref "U6") (pin "1") (pinfunction "1_1") (pintype "passive"))
      (node (ref "U6") (pin "4") (pinfunction "4_4") (pintype "passive"))
    )
    (net (code "71") (name "unconnected-(J10-Pad5)") (class "Default")
      (node (ref "J10") (pin "5") (pinfunction "5_5") (pintype "passive+no_connect"))
    )
    (net (code "72") (name "unconnected-(J10-Pad7)") (class "Default")
      (node (ref "J10") (pin "7") (pinfunction "7_7") (pintype "passive+no_connect"))
    )
    (net (code "73") (name "unconnected-(J10-Pad8)") (class "Default")
      (node (ref "J10") (pin "8") (pinfunction "8_8") (pintype "passive+no_connect"))
    )
    (net (code "74") (name "unconnected-(J10-Pad9)") (class "Default")
      (node (ref "J10") (pin "9") (pinfunction "9_9") (pintype "passive"))
    )
    (net (code "75") (name "unconnected-(J10-Pad10)") (class "Default")
      (node (ref "J10") (pin "10") (pinfunction "10_10") (pintype "passive"))
    )
    (net (code "76") (name "unconnected-(J10-Pad16)") (class "Default")
      (node (ref "J10") (pin "16") (pinfunction "16_16") (pintype "passive+no_connect"))
    )
    (net (code "77") (name "unconnected-(J10-Pad18)") (class "Default")
      (node (ref "J10") (pin "18") (pinfunction "18_18") (pintype "passive+no_connect"))
    )
    (net (code "78") (name "unconnected-(J11-Pad6)") (class "Default")
      (node (ref "J11") (pin "6") (pinfunction "6_6") (pintype "passive+no_connect"))
    )
    (net (code "79") (name "unconnected-(J11-Pad7)") (class "Default")
      (node (ref "J11") (pin "7") (pinfunction "7_7") (pintype "passive+no_connect"))
    )
    (net (code "80") (name "unconnected-(J11-Pad8)") (class "Default")
      (node (ref "J11") (pin "8") (pinfunction "8_8") (pintype "passive+no_connect"))
    )
    (net (code "81") (name "unconnected-(J11-Pad10)") (class "Default")
      (node (ref "J11") (pin "10") (pinfunction "10_10") (pintype "passive+no_connect"))
    )
    (net (code "82") (name "unconnected-(J11-Pad13)") (class "Default")
      (node (ref "J11") (pin "13") (pinfunction "13_13") (pintype "passive+no_connect"))
    )
    (net (code "83") (name "unconnected-(J11-Pad14)") (class "Default")
      (node (ref "J11") (pin "14") (pinfunction "14_14") (pintype "passive+no_connect"))
    )
    (net (code "84") (name "unconnected-(J11-Pad15)") (class "Default")
      (node (ref "J11") (pin "15") (pinfunction "15_15") (pintype "passive+no_connect"))
    )
    (net (code "85") (name "unconnected-(J11-Pad17)") (class "Default")
      (node (ref "J11") (pin "17") (pinfunction "17_17") (pintype "passive+no_connect"))
    )
    (net (code "86") (name "unconnected-(J11-Pad18)") (class "Default")
      (node (ref "J11") (pin "18") (pinfunction "18_18") (pintype "passive+no_connect"))
    )
    (net (code "87") (name "unconnected-(J11-Pad19)") (class "Default")
      (node (ref "J11") (pin "19") (pinfunction "19_19") (pintype "passive+no_connect"))
    )
    (net (code "88") (name "unconnected-(J11-Pad20)") (class "Default")
      (node (ref "J11") (pin "20") (pinfunction "20_20") (pintype "passive+no_connect"))
    )
    (net (code "89") (name "unconnected-(J12-Pad2)") (class "Default")
      (node (ref "J12") (pin "2") (pinfunction "2_2") (pintype "passive"))
    )
    (net (code "90") (name "unconnected-(J12-Pad11)") (class "Default")
      (node (ref "J12") (pin "11") (pinfunction "11_11") (pintype "passive+no_connect"))
    )
    (net (code "91") (name "unconnected-(J12-Pad12)") (class "Default")
      (node (ref "J12") (pin "12") (pinfunction "12_12") (pintype "passive+no_connect"))
    )
    (net (code "92") (name "unconnected-(J12-Pad13)") (class "Default")
      (node (ref "J12") (pin "13") (pinfunction "13_13") (pintype "passive+no_connect"))
    )
    (net (code "93") (name "unconnected-(J12-Pad14)") (class "Default")
      (node (ref "J12") (pin "14") (pinfunction "14_14") (pintype "passive+no_connect"))
    )
    (net (code "94") (name "unconnected-(J12-Pad15)") (class "Default")
      (node (ref "J12") (pin "15") (pinfunction "15_15") (pintype "passive+no_connect"))
    )
    (net (code "95") (name "unconnected-(J12-Pad16)") (class "Default")
      (node (ref "J12") (pin "16") (pinfunction "16_16") (pintype "passive+no_connect"))
    )
    (net (code "96") (name "unconnected-(R24-Pad1)") (class "Default")
      (node (ref "R24") (pin "1") (pinfunction "1_1") (pintype "passive+no_connect"))
    )
    (net (code "97") (name "unconnected-(U1-NR{slash}FB-Pad4)") (class "Default")
      (node (ref "U1") (pin "4") (pinfunction "NR/FB_4") (pintype "passive"))
    )
    (net (code "98") (name "unconnected-(U2-OSC-Pad7)") (class "Default")
      (node (ref "U2") (pin "7") (pinfunction "OSC_7") (pintype "passive+no_connect"))
    )
  )
)
